# STM32H730_PINOUT.net
KiCad netlist of a schematic drawn in Altium Designer
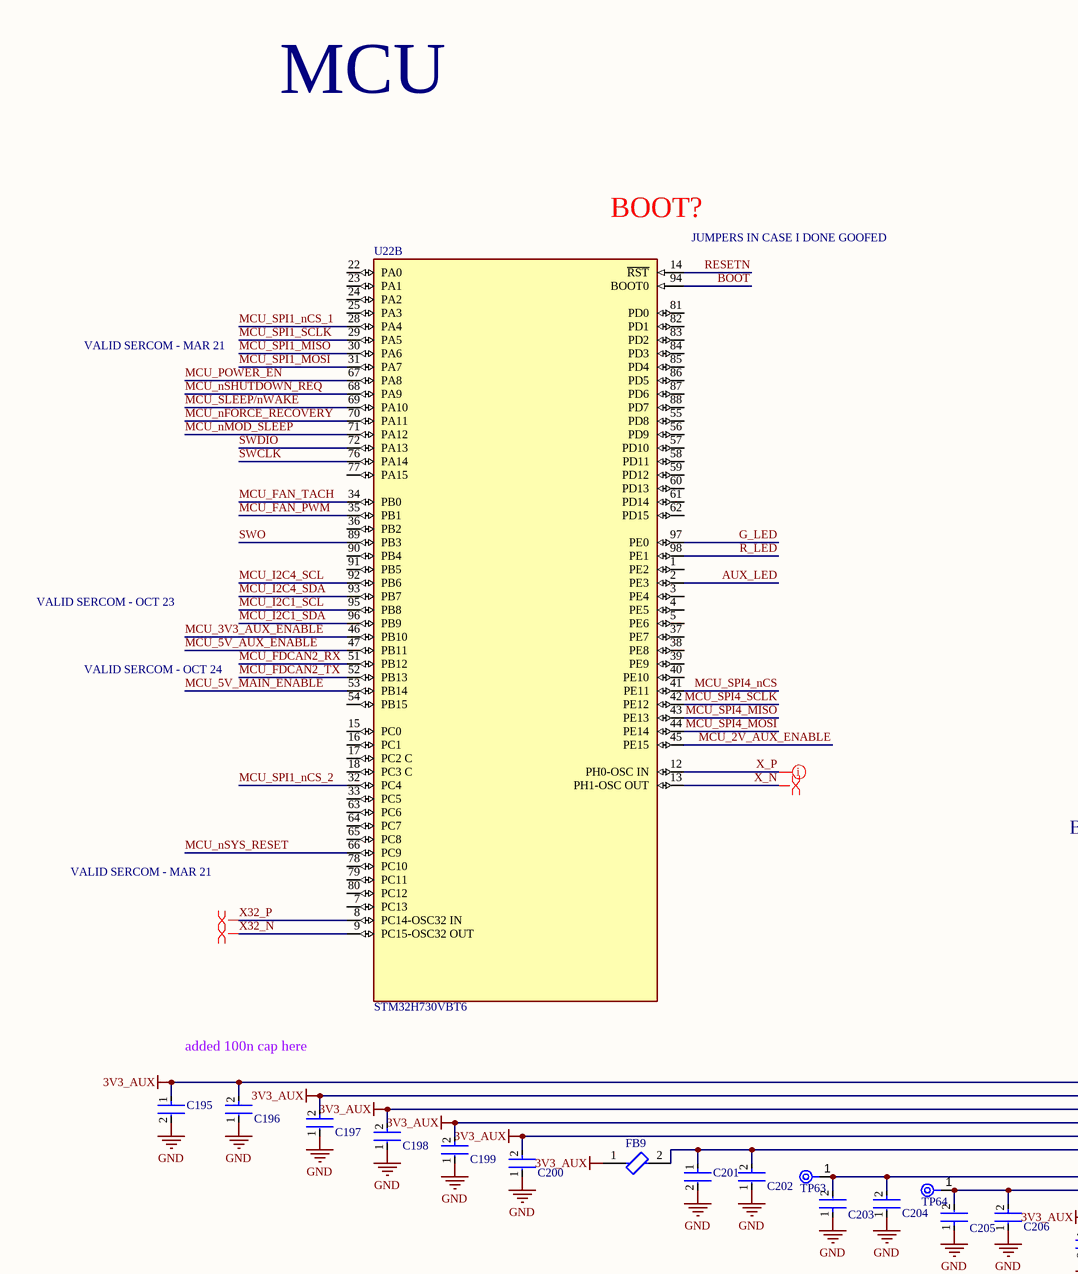
[diagram p0: STM32H730_PINOUT.SchDoc, top left]
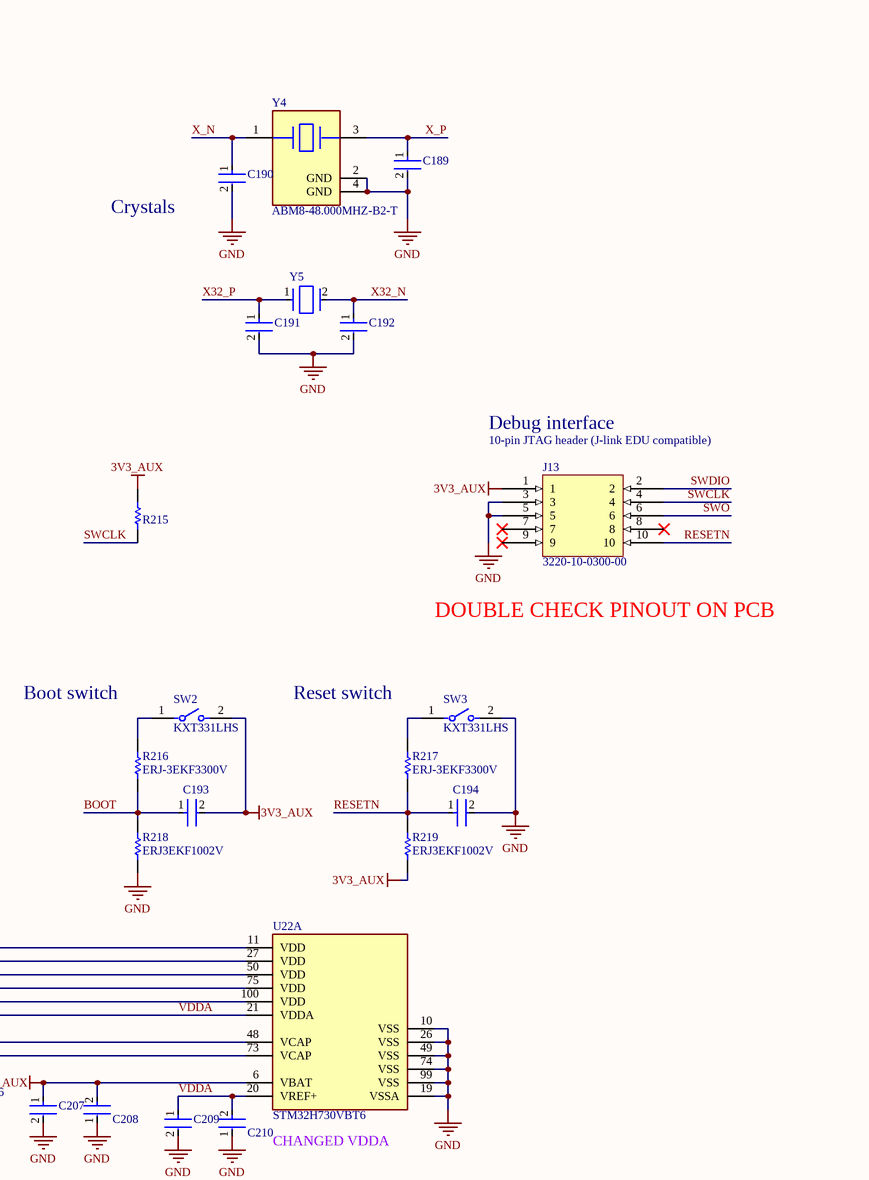
[diagram p1: STM32H730_PINOUT.SchDoc, top middle]
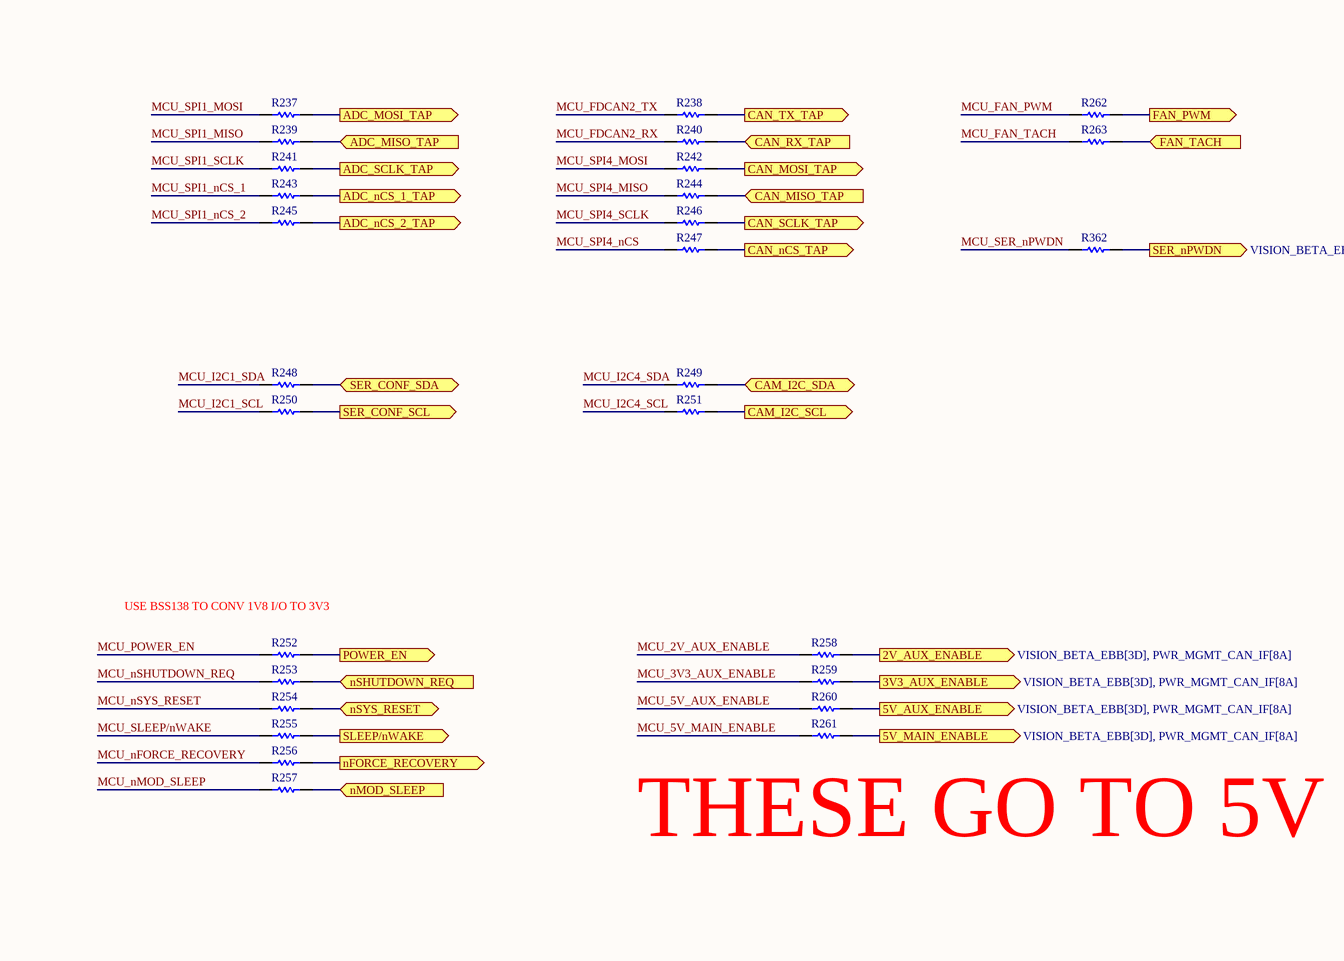
[diagram p2: STM32H730_PINOUT.SchDoc, top right]
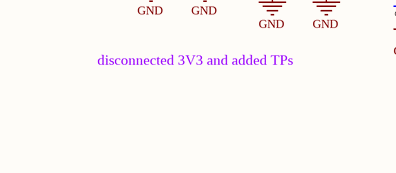
[diagram p3: STM32H730_PINOUT.SchDoc, bottom left]
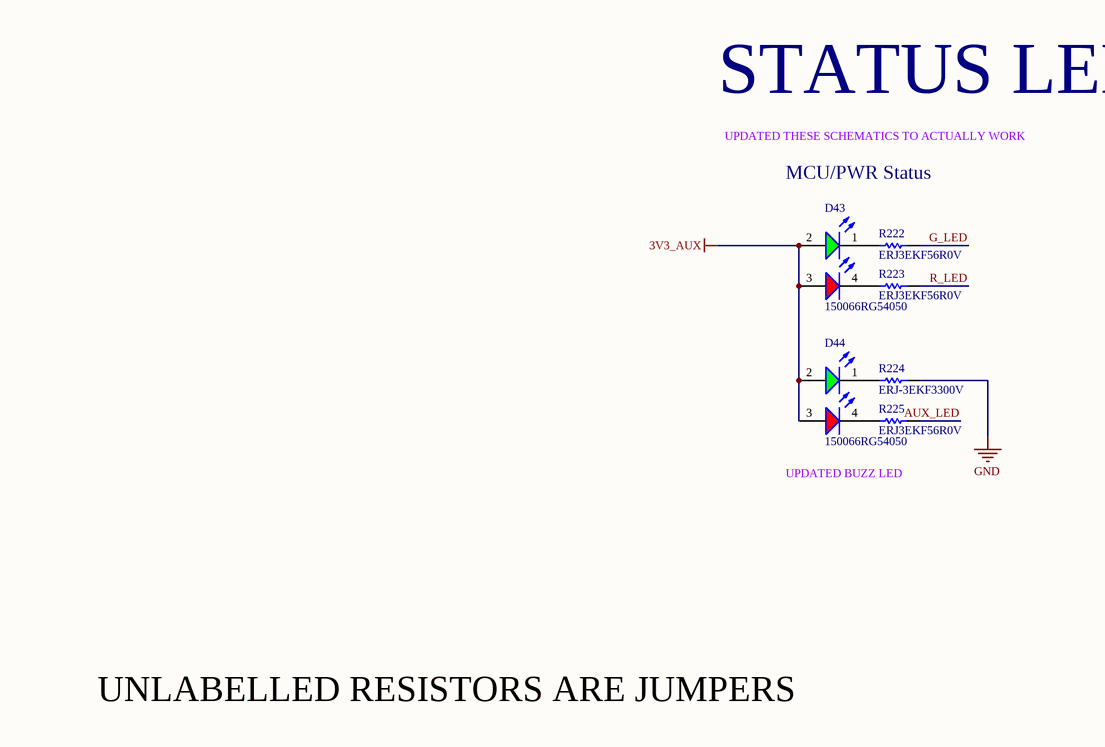
[diagram p4: STM32H730_PINOUT.SchDoc, bottom right]

(export (version "E")
  (design (tool "Eeschema 10.0.6"))
  (components
    (comp (ref "C189")
      (value "C0402C689C5GACTU")
      (footprint "FP-C0402-BB-MFG")
      (description "CAP CER 6.8PF 50V NP0 0402")
      (fields
        (field (name "OCTOPART") "https://octopart.com/c0402c689c5gactu-kemet-9143567")
        (field (name "MANUFACTURER") "Kemet")
      )
      (libsource (lib "Altium Content Vault") (part "b4654b650e69147ec39a6b967a45e02"))
    )
    (comp (ref "C190")
      (value "C0402C689C5GACTU")
      (footprint "FP-C0402-BB-MFG")
      (description "CAP CER 6.8PF 50V NP0 0402")
      (fields
        (field (name "OCTOPART") "https://octopart.com/c0402c689c5gactu-kemet-9143567")
        (field (name "MANUFACTURER") "Kemet")
      )
      (libsource (lib "Altium Content Vault") (part "b4654b650e69147ec39a6b967a45e02"))
    )
    (comp (ref "C191")
      (value "04025A180FAT2A")
      (footprint "FP-0402-L_1_0_1-W_0_5_0_1-IPC_A")
      (description "General Purpose Ceramic Capacitor, 0402, 18pF, 1%, C0G, 30ppm/°C, 50V")
      (fields (field (name "TOLERANCE") "1%"))
      (libsource (lib "Altium Content Vault") (part "b4654b650e69147ec39a6b967a45e02"))
    )
    (comp (ref "C192")
      (value "04025A180FAT2A")
      (footprint "FP-0402-L_1_0_1-W_0_5_0_1-IPC_A")
      (description "General Purpose Ceramic Capacitor, 0402, 18pF, 1%, C0G, 30ppm/°C, 50V")
      (fields (field (name "TOLERANCE") "1%"))
      (libsource (lib "Altium Content Vault") (part "b4654b650e69147ec39a6b967a45e02"))
    )
    (comp (ref "C193")
      (value "C0402C104K8PACTU")
      (footprint "FP-C0402-BB-MFG")
      (description "CAP CER 0.1UF 10V X5R 0402")
      (fields (field (name "MANUFACTURER") "Kemet") (field (name "TOLERANCE") "0.1"))
      (libsource (lib "Altium Content Vault") (part "b4654b650e69147ec39a6b967a45e02"))
    )
    (comp (ref "C194")
      (value "C0402C104K8PACTU")
      (footprint "FP-C0402-BB-MFG")
      (description "CAP CER 0.1UF 10V X5R 0402")
      (fields (field (name "MANUFACTURER") "Kemet") (field (name "TOLERANCE") "0.1"))
      (libsource (lib "Altium Content Vault") (part "b4654b650e69147ec39a6b967a45e02"))
    )
    (comp (ref "C195")
      (value "C1005X5R1A475K050BC")
      (footprint "FP-C1005-050-0_15-MFG")
      (description "CAP CER 4.7UF 10V X5R 0402")
      (fields (field (name "TOLERANCE") "10%"))
      (libsource (lib "Altium Content Vault") (part "b4654b650e69147ec39a6b967a45e02"))
    )
    (comp (ref "C196")
      (value "GRM155R71C104KA88D")
      (footprint "FP-GRM15-MFG")
      (description "CAP CER 0.1UF 16V X7R 0402")
      (fields
        (field (name "TOLERANCE") "10%")
        (field (name "OCTOPART") "https://octopart.com/grm155r71c104ka88d-murata-196880")
      )
      (libsource (lib "Altium Content Vault") (part "236180d848d6139a670b325ea6854c9"))
    )
    (comp (ref "C197")
      (value "GRM155R71C104KA88D")
      (footprint "FP-GRM15-MFG")
      (description "CAP CER 0.1UF 16V X7R 0402")
      (fields
        (field (name "TOLERANCE") "10%")
        (field (name "OCTOPART") "https://octopart.com/grm155r71c104ka88d-murata-196880")
      )
      (libsource (lib "Altium Content Vault") (part "236180d848d6139a670b325ea6854c9"))
    )
    (comp (ref "C198")
      (value "GRM155R71C104KA88D")
      (footprint "FP-GRM15-MFG")
      (description "CAP CER 0.1UF 16V X7R 0402")
      (fields
        (field (name "TOLERANCE") "10%")
        (field (name "OCTOPART") "https://octopart.com/grm155r71c104ka88d-murata-196880")
      )
      (libsource (lib "Altium Content Vault") (part "236180d848d6139a670b325ea6854c9"))
    )
    (comp (ref "C199")
      (value "GRM155R71C104KA88D")
      (footprint "FP-GRM15-MFG")
      (description "CAP CER 0.1UF 16V X7R 0402")
      (fields
        (field (name "TOLERANCE") "10%")
        (field (name "OCTOPART") "https://octopart.com/grm155r71c104ka88d-murata-196880")
      )
      (libsource (lib "Altium Content Vault") (part "236180d848d6139a670b325ea6854c9"))
    )
    (comp (ref "C200")
      (value "GRM155R71C104KA88D")
      (footprint "FP-GRM15-MFG")
      (description "CAP CER 0.1UF 16V X7R 0402")
      (fields
        (field (name "TOLERANCE") "10%")
        (field (name "OCTOPART") "https://octopart.com/grm155r71c104ka88d-murata-196880")
      )
      (libsource (lib "Altium Content Vault") (part "236180d848d6139a670b325ea6854c9"))
    )
    (comp (ref "C201")
      (value "EMK105BJ105KV-F")
      (footprint "FP-0402-L_1_0_0_05-W_0_5-IPC_A")
      (description "None")
      (fields (field (name "TOLERANCE") "10%"))
      (libsource (lib "Altium Content Vault") (part "b4654b650e69147ec39a6b967a45e02"))
    )
    (comp (ref "C202")
      (value "GRM155R71C104KA88D")
      (footprint "FP-GRM15-MFG")
      (description "CAP CER 0.1UF 16V X7R 0402")
      (fields
        (field (name "TOLERANCE") "10%")
        (field (name "OCTOPART") "https://octopart.com/grm155r71c104ka88d-murata-196880")
      )
      (libsource (lib "Altium Content Vault") (part "236180d848d6139a670b325ea6854c9"))
    )
    (comp (ref "C203")
      (value "C1005X7S1A225K050BC")
      (footprint "FP-C1005-050-0_15-0_1-MFG")
      (description "CAP CER 2.2UF 10V X7S 0402")
      (fields (field (name "TOLERANCE") "10%"))
      (libsource (lib "Altium Content Vault") (part "b4654b650e69147ec39a6b967a45e02"))
    )
    (comp (ref "C204")
      (value "GRM155R71C104KA88D")
      (footprint "FP-GRM15-MFG")
      (description "CAP CER 0.1UF 16V X7R 0402")
      (fields
        (field (name "TOLERANCE") "10%")
        (field (name "OCTOPART") "https://octopart.com/grm155r71c104ka88d-murata-196880")
      )
      (libsource (lib "Altium Content Vault") (part "236180d848d6139a670b325ea6854c9"))
    )
    (comp (ref "C205")
      (value "C1005X7S1A225K050BC")
      (footprint "FP-C1005-050-0_15-0_1-MFG")
      (description "CAP CER 2.2UF 10V X7S 0402")
      (fields (field (name "TOLERANCE") "10%"))
      (libsource (lib "Altium Content Vault") (part "b4654b650e69147ec39a6b967a45e02"))
    )
    (comp (ref "C206")
      (value "GRM155R71C104KA88D")
      (footprint "FP-GRM15-MFG")
      (description "CAP CER 0.1UF 16V X7R 0402")
      (fields
        (field (name "TOLERANCE") "10%")
        (field (name "OCTOPART") "https://octopart.com/grm155r71c104ka88d-murata-196880")
      )
      (libsource (lib "Altium Content Vault") (part "236180d848d6139a670b325ea6854c9"))
    )
    (comp (ref "C207")
      (value "EMK105BJ105KV-F")
      (footprint "FP-0402-L_1_0_0_05-W_0_5-IPC_A")
      (description "None")
      (fields (field (name "TOLERANCE") "10%"))
      (libsource (lib "Altium Content Vault") (part "b4654b650e69147ec39a6b967a45e02"))
    )
    (comp (ref "C208")
      (value "GRM155R71C104KA88D")
      (footprint "FP-GRM15-MFG")
      (description "CAP CER 0.1UF 16V X7R 0402")
      (fields
        (field (name "TOLERANCE") "10%")
        (field (name "OCTOPART") "https://octopart.com/grm155r71c104ka88d-murata-196880")
      )
      (libsource (lib "Altium Content Vault") (part "236180d848d6139a670b325ea6854c9"))
    )
    (comp (ref "C209")
      (value "EMK105BJ105KV-F")
      (footprint "FP-0402-L_1_0_0_05-W_0_5-IPC_A")
      (description "None")
      (fields (field (name "TOLERANCE") "10%"))
      (libsource (lib "Altium Content Vault") (part "b4654b650e69147ec39a6b967a45e02"))
    )
    (comp (ref "C210")
      (value "GRM155R71C104KA88D")
      (footprint "FP-GRM15-MFG")
      (description "CAP CER 0.1UF 16V X7R 0402")
      (fields
        (field (name "TOLERANCE") "10%")
        (field (name "OCTOPART") "https://octopart.com/grm155r71c104ka88d-murata-196880")
      )
      (libsource (lib "Altium Content Vault") (part "236180d848d6139a670b325ea6854c9"))
    )
    (comp (ref "D43")
      (value "150066RG54050")
      (footprint "WL-SBCD_0606")
      (description "Led, Red/Grn, 180Mcd/230Mcd, 624Nm/525Nm Rohs Compliant: Yes")
      (fields (field (name "SOURCE") "rgled.SchLib"))
      (libsource (lib "Space Concordia") (part "CMP-004-00034-2"))
    )
    (comp (ref "D44")
      (value "150066RG54050")
      (footprint "WL-SBCD_0606")
      (description "Led, Red/Grn, 180Mcd/230Mcd, 624Nm/525Nm Rohs Compliant: Yes")
      (fields (field (name "SOURCE") "rgled.SchLib"))
      (libsource (lib "Space Concordia") (part "CMP-004-00034-2"))
    )
    (comp (ref "FB9")
      (value "BLM15PX601SN1D")
      (footprint "FP-BLM15-0_05-MFG")
      (description "Chip Ferrite Bead, 0402, 600Ω @ 100MHz, 0.23Ω, 25%, 900mA")
      (fields (field (name "TOLERANCE") "25%"))
      (libsource (lib "Altium Content Vault") (part "5f30dd21d616792df468990f7003faa"))
    )
    (comp (ref "J13")
      (value "3220-10-0300-00")
      (footprint "3220-10-0300-00-Footprint-1")
      (description "CONN HEADER SMD 10POS 1.27MM")
      (libsource (lib "Space Concordia") (part "3220-10-0300-00"))
    )
    (comp (ref "R215")
      (value "ERJ3EKF1002V")
      (footprint "RESC1609X55X30LL15T15")
      (description "Chip Resistor, 10 KOhm, +/- 1%, 0.1 W, -55 to 155 degC, 0603 (1608 Metric), RoHS, Tape and Reel")
      (fields (field (name "TOLERANCE") "1%") (field (name "MANUFACTURER") "Panasonic"))
      (libsource (lib "Altium Content Vault") (part "RES-2"))
    )
    (comp (ref "R216")
      (value "ERJ-3EKF3300V")
      (footprint "RESC1608X55X30LL15T15")
      (description "Chip Resistor, 330 Ohm, +/- 1%, 0.1 W, -55 to 155 degC, 0603 (1608 Metric), RoHS, Tape and Reel")
      (libsource (lib "Altium Content Vault") (part "RES-2"))
    )
    (comp (ref "R217")
      (value "ERJ-3EKF3300V")
      (footprint "RESC1608X55X30LL15T15")
      (description "Chip Resistor, 330 Ohm, +/- 1%, 0.1 W, -55 to 155 degC, 0603 (1608 Metric), RoHS, Tape and Reel")
      (libsource (lib "Altium Content Vault") (part "RES-2"))
    )
    (comp (ref "R218")
      (value "ERJ3EKF1002V")
      (footprint "RESC1609X55X30LL15T15")
      (description "Chip Resistor, 10 KOhm, +/- 1%, 0.1 W, -55 to 155 degC, 0603 (1608 Metric), RoHS, Tape and Reel")
      (fields (field (name "TOLERANCE") "1%") (field (name "MANUFACTURER") "Panasonic"))
      (libsource (lib "Altium Content Vault") (part "RES-2"))
    )
    (comp (ref "R219")
      (value "ERJ3EKF1002V")
      (footprint "RESC1609X55X30LL15T15")
      (description "Chip Resistor, 10 KOhm, +/- 1%, 0.1 W, -55 to 155 degC, 0603 (1608 Metric), RoHS, Tape and Reel")
      (fields (field (name "TOLERANCE") "1%") (field (name "MANUFACTURER") "Panasonic"))
      (libsource (lib "Altium Content Vault") (part "RES-2"))
    )
    (comp (ref "R222")
      (value "ERJ3EKF56R0V")
      (footprint "RESC1608X55X30NL15T15")
      (fields (field (name "MANUFACTURER") "Panasonic"))
      (libsource (lib "Altium Content Vault") (part "RES"))
    )
    (comp (ref "R223")
      (value "ERJ3EKF56R0V")
      (footprint "RESC1608X55X30NL15T15")
      (fields (field (name "MANUFACTURER") "Panasonic"))
      (libsource (lib "Altium Content Vault") (part "RES"))
    )
    (comp (ref "R224")
      (value "ERJ-3EKF3300V")
      (footprint "RESC1608X55X30LL15T15")
      (description "Chip Resistor, 330 Ohm, +/- 1%, 0.1 W, -55 to 155 degC, 0603 (1608 Metric), RoHS, Tape and Reel")
      (libsource (lib "Altium Content Vault") (part "RES-2"))
    )
    (comp (ref "R225")
      (value "ERJ3EKF56R0V")
      (footprint "RESC1608X55X30NL15T15")
      (fields (field (name "MANUFACTURER") "Panasonic"))
      (libsource (lib "Altium Content Vault") (part "RES"))
    )
    (comp (ref "R237")
      (value "0402 JUMPER")
      (footprint "RESC1005X40X25ML05T05")
      (description "READ THE NAME")
      (libsource (lib "Space Concordia") (part "CMP-009-00206-2"))
    )
    (comp (ref "R238")
      (value "0402 JUMPER")
      (footprint "RESC1005X40X25ML05T05")
      (description "READ THE NAME")
      (libsource (lib "Space Concordia") (part "CMP-009-00206-2"))
    )
    (comp (ref "R239")
      (value "0402 JUMPER")
      (footprint "RESC1005X40X25ML05T05")
      (description "READ THE NAME")
      (libsource (lib "Space Concordia") (part "CMP-009-00206-2"))
    )
    (comp (ref "R240")
      (value "0402 JUMPER")
      (footprint "RESC1005X40X25ML05T05")
      (description "READ THE NAME")
      (libsource (lib "Space Concordia") (part "CMP-009-00206-2"))
    )
    (comp (ref "R241")
      (value "0402 JUMPER")
      (footprint "RESC1005X40X25ML05T05")
      (description "READ THE NAME")
      (libsource (lib "Space Concordia") (part "CMP-009-00206-2"))
    )
    (comp (ref "R242")
      (value "0402 JUMPER")
      (footprint "RESC1005X40X25ML05T05")
      (description "READ THE NAME")
      (libsource (lib "Space Concordia") (part "CMP-009-00206-2"))
    )
    (comp (ref "R243")
      (value "0402 JUMPER")
      (footprint "RESC1005X40X25ML05T05")
      (description "READ THE NAME")
      (libsource (lib "Space Concordia") (part "CMP-009-00206-2"))
    )
    (comp (ref "R244")
      (value "0402 JUMPER")
      (footprint "RESC1005X40X25ML05T05")
      (description "READ THE NAME")
      (libsource (lib "Space Concordia") (part "CMP-009-00206-2"))
    )
    (comp (ref "R245")
      (value "0402 JUMPER")
      (footprint "RESC1005X40X25ML05T05")
      (description "READ THE NAME")
      (libsource (lib "Space Concordia") (part "CMP-009-00206-2"))
    )
    (comp (ref "R246")
      (value "0402 JUMPER")
      (footprint "RESC1005X40X25ML05T05")
      (description "READ THE NAME")
      (libsource (lib "Space Concordia") (part "CMP-009-00206-2"))
    )
    (comp (ref "R247")
      (value "0402 JUMPER")
      (footprint "RESC1005X40X25ML05T05")
      (description "READ THE NAME")
      (libsource (lib "Space Concordia") (part "CMP-009-00206-2"))
    )
    (comp (ref "R248")
      (value "0402 JUMPER")
      (footprint "RESC1005X40X25ML05T05")
      (description "READ THE NAME")
      (libsource (lib "Space Concordia") (part "CMP-009-00206-2"))
    )
    (comp (ref "R249")
      (value "0402 JUMPER")
      (footprint "RESC1005X40X25ML05T05")
      (description "READ THE NAME")
      (libsource (lib "Space Concordia") (part "CMP-009-00206-2"))
    )
    (comp (ref "R250")
      (value "0402 JUMPER")
      (footprint "RESC1005X40X25ML05T05")
      (description "READ THE NAME")
      (libsource (lib "Space Concordia") (part "CMP-009-00206-2"))
    )
    (comp (ref "R251")
      (value "0402 JUMPER")
      (footprint "RESC1005X40X25ML05T05")
      (description "READ THE NAME")
      (libsource (lib "Space Concordia") (part "CMP-009-00206-2"))
    )
    (comp (ref "R252")
      (value "0402 JUMPER")
      (footprint "RESC1005X40X25ML05T05")
      (description "READ THE NAME")
      (libsource (lib "Space Concordia") (part "CMP-009-00206-2"))
    )
    (comp (ref "R253")
      (value "0402 JUMPER")
      (footprint "RESC1005X40X25ML05T05")
      (description "READ THE NAME")
      (libsource (lib "Space Concordia") (part "CMP-009-00206-2"))
    )
    (comp (ref "R254")
      (value "0402 JUMPER")
      (footprint "RESC1005X40X25ML05T05")
      (description "READ THE NAME")
      (libsource (lib "Space Concordia") (part "CMP-009-00206-2"))
    )
    (comp (ref "R255")
      (value "0402 JUMPER")
      (footprint "RESC1005X40X25ML05T05")
      (description "READ THE NAME")
      (libsource (lib "Space Concordia") (part "CMP-009-00206-2"))
    )
    (comp (ref "R256")
      (value "0402 JUMPER")
      (footprint "RESC1005X40X25ML05T05")
      (description "READ THE NAME")
      (libsource (lib "Space Concordia") (part "CMP-009-00206-2"))
    )
    (comp (ref "R257")
      (value "0402 JUMPER")
      (footprint "RESC1005X40X25ML05T05")
      (description "READ THE NAME")
      (libsource (lib "Space Concordia") (part "CMP-009-00206-2"))
    )
    (comp (ref "R258")
      (value "0402 JUMPER")
      (footprint "RESC1005X40X25ML05T05")
      (description "READ THE NAME")
      (libsource (lib "Space Concordia") (part "CMP-009-00206-2"))
    )
    (comp (ref "R259")
      (value "0402 JUMPER")
      (footprint "RESC1005X40X25ML05T05")
      (description "READ THE NAME")
      (libsource (lib "Space Concordia") (part "CMP-009-00206-2"))
    )
    (comp (ref "R260")
      (value "0402 JUMPER")
      (footprint "RESC1005X40X25ML05T05")
      (description "READ THE NAME")
      (libsource (lib "Space Concordia") (part "CMP-009-00206-2"))
    )
    (comp (ref "R261")
      (value "0402 JUMPER")
      (footprint "RESC1005X40X25ML05T05")
      (description "READ THE NAME")
      (libsource (lib "Space Concordia") (part "CMP-009-00206-2"))
    )
    (comp (ref "R262")
      (value "0402 JUMPER")
      (footprint "RESC1005X40X25ML05T05")
      (description "READ THE NAME")
      (libsource (lib "Space Concordia") (part "CMP-009-00206-2"))
    )
    (comp (ref "R263")
      (value "0402 JUMPER")
      (footprint "RESC1005X40X25ML05T05")
      (description "READ THE NAME")
      (libsource (lib "Space Concordia") (part "CMP-009-00206-2"))
    )
    (comp (ref "R362")
      (value "0402 JUMPER")
      (footprint "RESC1005X40X25ML05T05")
      (description "READ THE NAME")
      (libsource (lib "Space Concordia") (part "CMP-009-00206-2"))
    )
    (comp (ref "SW2")
      (value "KXT331LHS")
      (footprint "FP-KXT331LHS-MFG")
      (description "SWITCH TACTILE SPST-NO 0.02A 15V")
      (libsource (lib "Altium Content Vault") (part "bb27bde45df87f1f469753f287ef5ae"))
    )
    (comp (ref "SW3")
      (value "KXT331LHS")
      (footprint "FP-KXT331LHS-MFG")
      (description "SWITCH TACTILE SPST-NO 0.02A 15V")
      (libsource (lib "Altium Content Vault") (part "bb27bde45df87f1f469753f287ef5ae"))
    )
    (comp (ref "TP63")
      (value "TPAD6R")
      (footprint "New footprint 1")
      (description "Test Point .6mm")
      (libsource (lib "Space Concordia") (part "TP"))
    )
    (comp (ref "TP64")
      (value "TPAD6R")
      (footprint "New footprint 1")
      (description "Test Point .6mm")
      (libsource (lib "Space Concordia") (part "TP"))
    )
    (comp (ref "U22")
      (value "STM32H730VBT6")
      (footprint "FP-LQFP100-1L-IPC_C")
      (description "IC MCU 32BIT 128KB FLASH 100LQFP")
      (libsource (lib "Altium Content Vault") (part "44dc6501260a4d92b846760feb66c20"))
    )
    (comp (ref "Y4")
      (value "ABM8-48.000MHZ-B2-T")
      (footprint "FP-ABM8-MFG")
      (description "Crystal 48MHz ±20ppm 18pF SMD-4 3.2mm x 2.5mm")
      (fields (field (name "TOLERANCE") "20ppm"))
      (libsource (lib "Altium Content Vault") (part "dfdb7f9a12507849fb681da9a70121c"))
    )
    (comp (ref "Y5")
      (value "ECS-.327-12.5-1210-TR")
      (footprint "FP-ECX-1210-MFG")
      (description "CRYSTAL 32.7680KHZ 12.5PF SMD")
      (fields
        (field (name "OCTOPART") "https://octopart.com/ecs-.327-12.5-1210-tr-ecs+international-81221340")
        (field (name "TOLERANCE") "20ppm")
      )
      (libsource (lib "Altium Content Vault") (part "99724985039315a44fd0d1401b84e49"))
    )
  )
  (nets
    (net (code "1") (name "/2V_AUX_ENABLE") (class "Default")
      (node (ref "R258") (pin "2") (pinfunction "2_2") (pintype "passive"))
    )
    (net (code "2") (name "/3V3_AUX_ENABLE") (class "Default")
      (node (ref "R259") (pin "2") (pinfunction "2_2") (pintype "passive"))
    )
    (net (code "3") (name "/5V_AUX_ENABLE") (class "Default")
      (node (ref "R260") (pin "2") (pinfunction "2_2") (pintype "passive"))
    )
    (net (code "4") (name "/5V_MAIN_ENABLE") (class "Default")
      (node (ref "R261") (pin "2") (pinfunction "2_2") (pintype "passive"))
    )
    (net (code "5") (name "/ADC_MISO_TAP") (class "Default")
      (node (ref "R239") (pin "2") (pinfunction "2_2") (pintype "passive"))
    )
    (net (code "6") (name "/ADC_MOSI_TAP") (class "Default")
      (node (ref "R237") (pin "2") (pinfunction "2_2") (pintype "passive"))
    )
    (net (code "7") (name "/ADC_SCLK_TAP") (class "Default")
      (node (ref "R241") (pin "2") (pinfunction "2_2") (pintype "passive"))
    )
    (net (code "8") (name "/ADC_nCS_1_TAP") (class "Default")
      (node (ref "R243") (pin "2") (pinfunction "2_2") (pintype "passive"))
    )
    (net (code "9") (name "/ADC_nCS_2_TAP") (class "Default")
      (node (ref "R245") (pin "2") (pinfunction "2_2") (pintype "passive"))
    )
    (net (code "10") (name "/AUX_LED") (class "Default")
      (node (ref "R225") (pin "1") (pinfunction "1_1") (pintype "passive"))
      (node (ref "U22") (pin "2") (pinfunction "PE3_2") (pintype "bidirectional"))
    )
    (net (code "11") (name "/BOOT") (class "Default")
      (node (ref "C193") (pin "1") (pinfunction "1_1") (pintype "passive"))
      (node (ref "R216") (pin "1") (pinfunction "1_1") (pintype "passive"))
      (node (ref "R218") (pin "2") (pinfunction "2_2") (pintype "passive"))
      (node (ref "U22") (pin "94") (pinfunction "BOOT0_94") (pintype "input"))
    )
    (net (code "12") (name "/CAM_I2C_SCL") (class "Default")
      (node (ref "R251") (pin "2") (pinfunction "2_2") (pintype "passive"))
    )
    (net (code "13") (name "/CAM_I2C_SDA") (class "Default")
      (node (ref "R249") (pin "2") (pinfunction "2_2") (pintype "passive"))
    )
    (net (code "14") (name "/CAN_MISO_TAP") (class "Default")
      (node (ref "R244") (pin "2") (pinfunction "2_2") (pintype "passive"))
    )
    (net (code "15") (name "/CAN_MOSI_TAP") (class "Default")
      (node (ref "R242") (pin "2") (pinfunction "2_2") (pintype "passive"))
    )
    (net (code "16") (name "/CAN_RX_TAP") (class "Default")
      (node (ref "R240") (pin "2") (pinfunction "2_2") (pintype "passive"))
    )
    (net (code "17") (name "/CAN_SCLK_TAP") (class "Default")
      (node (ref "R246") (pin "2") (pinfunction "2_2") (pintype "passive"))
    )
    (net (code "18") (name "/CAN_TX_TAP") (class "Default")
      (node (ref "R238") (pin "2") (pinfunction "2_2") (pintype "passive"))
    )
    (net (code "19") (name "/CAN_nCS_TAP") (class "Default")
      (node (ref "R247") (pin "2") (pinfunction "2_2") (pintype "passive"))
    )
    (net (code "20") (name "/FAN_PWM") (class "Default")
      (node (ref "R262") (pin "2") (pinfunction "2_2") (pintype "passive"))
    )
    (net (code "21") (name "/FAN_TACH") (class "Default")
      (node (ref "R263") (pin "2") (pinfunction "2_2") (pintype "passive"))
    )
    (net (code "22") (name "/G_LED") (class "Default")
      (node (ref "R222") (pin "1") (pinfunction "1_1") (pintype "passive"))
      (node (ref "U22") (pin "97") (pinfunction "PE0_97") (pintype "bidirectional"))
    )
    (net (code "23") (name "/MCU_2V_AUX_ENABLE") (class "Default")
      (node (ref "R258") (pin "1") (pinfunction "1_1") (pintype "passive"))
      (node (ref "U22") (pin "45") (pinfunction "PE15_45") (pintype "bidirectional"))
    )
    (net (code "24") (name "/MCU_3V3_AUX_ENABLE") (class "Default")
      (node (ref "R259") (pin "1") (pinfunction "1_1") (pintype "passive"))
      (node (ref "U22") (pin "46") (pinfunction "PB10_46") (pintype "bidirectional"))
    )
    (net (code "25") (name "/MCU_5V_AUX_ENABLE") (class "Default")
      (node (ref "R260") (pin "1") (pinfunction "1_1") (pintype "passive"))
      (node (ref "U22") (pin "47") (pinfunction "PB11_47") (pintype "bidirectional"))
    )
    (net (code "26") (name "/MCU_5V_MAIN_ENABLE") (class "Default")
      (node (ref "R261") (pin "1") (pinfunction "1_1") (pintype "passive"))
      (node (ref "U22") (pin "53") (pinfunction "PB14_53") (pintype "bidirectional"))
    )
    (net (code "27") (name "/MCU_FAN_PWM") (class "Default")
      (node (ref "R262") (pin "1") (pinfunction "1_1") (pintype "passive"))
      (node (ref "U22") (pin "35") (pinfunction "PB1_35") (pintype "bidirectional"))
    )
    (net (code "28") (name "/MCU_FAN_TACH") (class "Default")
      (node (ref "R263") (pin "1") (pinfunction "1_1") (pintype "passive"))
      (node (ref "U22") (pin "34") (pinfunction "PB0_34") (pintype "bidirectional"))
    )
    (net (code "29") (name "/MCU_FDCAN2_RX") (class "Default")
      (node (ref "R240") (pin "1") (pinfunction "1_1") (pintype "passive"))
      (node (ref "U22") (pin "51") (pinfunction "PB12_51") (pintype "bidirectional"))
    )
    (net (code "30") (name "/MCU_FDCAN2_TX") (class "Default")
      (node (ref "R238") (pin "1") (pinfunction "1_1") (pintype "passive"))
      (node (ref "U22") (pin "52") (pinfunction "PB13_52") (pintype "bidirectional"))
    )
    (net (code "31") (name "/MCU_I2C1_SCL") (class "Default")
      (node (ref "R250") (pin "1") (pinfunction "1_1") (pintype "passive"))
      (node (ref "U22") (pin "95") (pinfunction "PB8_95") (pintype "bidirectional"))
    )
    (net (code "32") (name "/MCU_I2C1_SDA") (class "Default")
      (node (ref "R248") (pin "1") (pinfunction "1_1") (pintype "passive"))
      (node (ref "U22") (pin "96") (pinfunction "PB9_96") (pintype "bidirectional"))
    )
    (net (code "33") (name "/MCU_I2C4_SCL") (class "Default")
      (node (ref "R251") (pin "1") (pinfunction "1_1") (pintype "passive"))
      (node (ref "U22") (pin "92") (pinfunction "PB6_92") (pintype "bidirectional"))
    )
    (net (code "34") (name "/MCU_I2C4_SDA") (class "Default")
      (node (ref "R249") (pin "1") (pinfunction "1_1") (pintype "passive"))
      (node (ref "U22") (pin "93") (pinfunction "PB7_93") (pintype "bidirectional"))
    )
    (net (code "35") (name "/MCU_POWER_EN") (class "Default")
      (node (ref "R252") (pin "1") (pinfunction "1_1") (pintype "passive"))
      (node (ref "U22") (pin "67") (pinfunction "PA8_67") (pintype "bidirectional"))
    )
    (net (code "36") (name "/MCU_SER_nPWDN") (class "Default")
      (node (ref "R362") (pin "1") (pinfunction "1_1") (pintype "passive"))
    )
    (net (code "37") (name "/MCU_SLEEP{slash}nWAKE") (class "Default")
      (node (ref "R255") (pin "1") (pinfunction "1_1") (pintype "passive"))
      (node (ref "U22") (pin "69") (pinfunction "PA10_69") (pintype "bidirectional"))
    )
    (net (code "38") (name "/MCU_SPI1_MISO") (class "Default")
      (node (ref "R239") (pin "1") (pinfunction "1_1") (pintype "passive"))
      (node (ref "U22") (pin "30") (pinfunction "PA6_30") (pintype "bidirectional"))
    )
    (net (code "39") (name "/MCU_SPI1_MOSI") (class "Default")
      (node (ref "R237") (pin "1") (pinfunction "1_1") (pintype "passive"))
      (node (ref "U22") (pin "31") (pinfunction "PA7_31") (pintype "bidirectional"))
    )
    (net (code "40") (name "/MCU_SPI1_SCLK") (class "Default")
      (node (ref "R241") (pin "1") (pinfunction "1_1") (pintype "passive"))
      (node (ref "U22") (pin "29") (pinfunction "PA5_29") (pintype "bidirectional"))
    )
    (net (code "41") (name "/MCU_SPI1_nCS_1") (class "Default")
      (node (ref "R243") (pin "1") (pinfunction "1_1") (pintype "passive"))
      (node (ref "U22") (pin "28") (pinfunction "PA4_28") (pintype "bidirectional"))
    )
    (net (code "42") (name "/MCU_SPI1_nCS_2") (class "Default")
      (node (ref "R245") (pin "1") (pinfunction "1_1") (pintype "passive"))
      (node (ref "U22") (pin "32") (pinfunction "PC4_32") (pintype "bidirectional"))
    )
    (net (code "43") (name "/MCU_SPI4_MISO") (class "Default")
      (node (ref "R244") (pin "1") (pinfunction "1_1") (pintype "passive"))
      (node (ref "U22") (pin "43") (pinfunction "PE13_43") (pintype "bidirectional"))
    )
    (net (code "44") (name "/MCU_SPI4_MOSI") (class "Default")
      (node (ref "R242") (pin "1") (pinfunction "1_1") (pintype "passive"))
      (node (ref "U22") (pin "44") (pinfunction "PE14_44") (pintype "bidirectional"))
    )
    (net (code "45") (name "/MCU_SPI4_SCLK") (class "Default")
      (node (ref "R246") (pin "1") (pinfunction "1_1") (pintype "passive"))
      (node (ref "U22") (pin "42") (pinfunction "PE12_42") (pintype "bidirectional"))
    )
    (net (code "46") (name "/MCU_SPI4_nCS") (class "Default")
      (node (ref "R247") (pin "1") (pinfunction "1_1") (pintype "passive"))
      (node (ref "U22") (pin "41") (pinfunction "PE11_41") (pintype "bidirectional"))
    )
    (net (code "47") (name "/MCU_nFORCE_RECOVERY") (class "Default")
      (node (ref "R256") (pin "1") (pinfunction "1_1") (pintype "passive"))
      (node (ref "U22") (pin "70") (pinfunction "PA11_70") (pintype "bidirectional"))
    )
    (net (code "48") (name "/MCU_nMOD_SLEEP") (class "Default")
      (node (ref "R257") (pin "1") (pinfunction "1_1") (pintype "passive"))
      (node (ref "U22") (pin "71") (pinfunction "PA12_71") (pintype "bidirectional"))
    )
    (net (code "49") (name "/MCU_nSHUTDOWN_REQ") (class "Default")
      (node (ref "R253") (pin "1") (pinfunction "1_1") (pintype "passive"))
      (node (ref "U22") (pin "68") (pinfunction "PA9_68") (pintype "bidirectional"))
    )
    (net (code "50") (name "/MCU_nSYS_RESET") (class "Default")
      (node (ref "R254") (pin "1") (pinfunction "1_1") (pintype "passive"))
      (node (ref "U22") (pin "66") (pinfunction "PC9_66") (pintype "bidirectional"))
    )
    (net (code "51") (name "/POWER_EN") (class "Default")
      (node (ref "R252") (pin "2") (pinfunction "2_2") (pintype "passive"))
    )
    (net (code "52") (name "/RESETN") (class "Default")
      (node (ref "C194") (pin "1") (pinfunction "1_1") (pintype "passive"))
      (node (ref "J13") (pin "10") (pinfunction "10_10") (pintype "input"))
      (node (ref "R217") (pin "1") (pinfunction "1_1") (pintype "passive"))
      (node (ref "R219") (pin "2") (pinfunction "2_2") (pintype "passive"))
      (node (ref "U22") (pin "14") (pinfunction "~{RST}_14") (pintype "input"))
    )
    (net (code "53") (name "/R_LED") (class "Default")
      (node (ref "R223") (pin "1") (pinfunction "1_1") (pintype "passive"))
      (node (ref "U22") (pin "98") (pinfunction "PE1_98") (pintype "bidirectional"))
    )
    (net (code "54") (name "/SER_CONF_SCL") (class "Default")
      (node (ref "R250") (pin "2") (pinfunction "2_2") (pintype "passive"))
    )
    (net (code "55") (name "/SER_CONF_SDA") (class "Default")
      (node (ref "R248") (pin "2") (pinfunction "2_2") (pintype "passive"))
    )
    (net (code "56") (name "/SER_nPWDN") (class "Default")
      (node (ref "R362") (pin "2") (pinfunction "2_2") (pintype "passive"))
    )
    (net (code "57") (name "/SLEEP{slash}nWAKE") (class "Default")
      (node (ref "R255") (pin "2") (pinfunction "2_2") (pintype "passive"))
    )
    (net (code "58") (name "/SWCLK") (class "Default")
      (node (ref "J13") (pin "4") (pinfunction "4_4") (pintype "input"))
      (node (ref "R215") (pin "2") (pinfunction "2_2") (pintype "passive"))
      (node (ref "U22") (pin "76") (pinfunction "PA14_76") (pintype "bidirectional"))
    )
    (net (code "59") (name "/SWDIO") (class "Default")
      (node (ref "J13") (pin "2") (pinfunction "2_2") (pintype "input"))
      (node (ref "U22") (pin "72") (pinfunction "PA13_72") (pintype "bidirectional"))
    )
    (net (code "60") (name "/SWO") (class "Default")
      (node (ref "J13") (pin "6") (pinfunction "6_6") (pintype "input"))
      (node (ref "U22") (pin "89") (pinfunction "PB3_89") (pintype "bidirectional"))
    )
    (net (code "61") (name "/VDDA") (class "Default")
      (node (ref "C201") (pin "1") (pinfunction "1_1") (pintype "passive"))
      (node (ref "C202") (pin "2") (pinfunction "2_2") (pintype "passive"))
      (node (ref "C209") (pin "1") (pinfunction "1_1") (pintype "passive"))
      (node (ref "C210") (pin "2") (pinfunction "2_2") (pintype "passive"))
      (node (ref "FB9") (pin "2") (pinfunction "2_2") (pintype "passive"))
      (node (ref "U22") (pin "20") (pinfunction "VREF+_20") (pintype "power_in"))
      (node (ref "U22") (pin "21") (pinfunction "VDDA_21") (pintype "power_in"))
    )
    (net (code "62") (name "/X32_N") (class "Default")
      (node (ref "C192") (pin "1") (pinfunction "1_1") (pintype "passive"))
      (node (ref "U22") (pin "9") (pinfunction "PC15-OSC32_OUT_9") (pintype "bidirectional"))
      (node (ref "Y5") (pin "2") (pinfunction "Out/In_2") (pintype "passive"))
    )
    (net (code "63") (name "/X32_P") (class "Default")
      (node (ref "C191") (pin "1") (pinfunction "1_1") (pintype "passive"))
      (node (ref "U22") (pin "8") (pinfunction "PC14-OSC32_IN_8") (pintype "bidirectional"))
      (node (ref "Y5") (pin "1") (pinfunction "In/Out_1") (pintype "passive"))
    )
    (net (code "64") (name "/X_N") (class "Default")
      (node (ref "C190") (pin "1") (pinfunction "1_1") (pintype "passive"))
      (node (ref "U22") (pin "13") (pinfunction "PH1-OSC_OUT_13") (pintype "bidirectional"))
      (node (ref "Y4") (pin "1") (pinfunction "1_1") (pintype "passive"))
    )
    (net (code "65") (name "/X_P") (class "Default")
      (node (ref "C189") (pin "1") (pinfunction "1_1") (pintype "passive"))
      (node (ref "U22") (pin "12") (pinfunction "PH0-OSC_IN_12") (pintype "bidirectional"))
      (node (ref "Y4") (pin "3") (pinfunction "3_3") (pintype "passive"))
    )
    (net (code "66") (name "/nFORCE_RECOVERY") (class "Default")
      (node (ref "R256") (pin "2") (pinfunction "2_2") (pintype "passive"))
    )
    (net (code "67") (name "/nMOD_SLEEP") (class "Default")
      (node (ref "R257") (pin "2") (pinfunction "2_2") (pintype "passive"))
    )
    (net (code "68") (name "/nSHUTDOWN_REQ") (class "Default")
      (node (ref "R253") (pin "2") (pinfunction "2_2") (pintype "passive"))
    )
    (net (code "69") (name "/nSYS_RESET") (class "Default")
      (node (ref "R254") (pin "2") (pinfunction "2_2") (pintype "passive"))
    )
    (net (code "70") (name "3V3_AUX") (class "Default")
      (node (ref "C193") (pin "2") (pinfunction "2_2") (pintype "passive"))
      (node (ref "C195") (pin "1") (pinfunction "1_1") (pintype "passive"))
      (node (ref "C196") (pin "2") (pinfunction "2_2") (pintype "passive"))
      (node (ref "C197") (pin "2") (pinfunction "2_2") (pintype "passive"))
      (node (ref "C198") (pin "2") (pinfunction "2_2") (pintype "passive"))
      (node (ref "C199") (pin "2") (pinfunction "2_2") (pintype "passive"))
      (node (ref "C200") (pin "2") (pinfunction "2_2") (pintype "passive"))
      (node (ref "C207") (pin "1") (pinfunction "1_1") (pintype "passive"))
      (node (ref "C208") (pin "2") (pinfunction "2_2") (pintype "passive"))
      (node (ref "D43") (pin "2") (pinfunction "A_2") (pintype "passive"))
      (node (ref "D43") (pin "3") (pinfunction "A_3") (pintype "passive"))
      (node (ref "D44") (pin "2") (pinfunction "A_2") (pintype "passive"))
      (node (ref "D44") (pin "3") (pinfunction "A_3") (pintype "passive"))
      (node (ref "FB9") (pin "1") (pinfunction "1_1") (pintype "passive"))
      (node (ref "J13") (pin "1") (pinfunction "1_1") (pintype "input"))
      (node (ref "R215") (pin "1") (pinfunction "1_1") (pintype "passive"))
      (node (ref "R219") (pin "1") (pinfunction "1_1") (pintype "passive"))
      (node (ref "SW2") (pin "2") (pinfunction "2_2") (pintype "passive"))
      (node (ref "U22") (pin "100") (pinfunction "VDD_100") (pintype "power_in"))
      (node (ref "U22") (pin "11") (pinfunction "VDD_11") (pintype "power_in"))
      (node (ref "U22") (pin "27") (pinfunction "VDD_27") (pintype "power_in"))
      (node (ref "U22") (pin "50") (pinfunction "VDD_50") (pintype "power_in"))
      (node (ref "U22") (pin "6") (pinfunction "VBAT_6") (pintype "power_in"))
      (node (ref "U22") (pin "75") (pinfunction "VDD_75") (pintype "power_in"))
    )
    (net (code "71") (name "GND") (class "Default")
      (node (ref "C189") (pin "2") (pinfunction "2_2") (pintype "passive"))
      (node (ref "C190") (pin "2") (pinfunction "2_2") (pintype "passive"))
      (node (ref "C191") (pin "2") (pinfunction "2_2") (pintype "passive"))
      (node (ref "C192") (pin "2") (pinfunction "2_2") (pintype "passive"))
      (node (ref "C194") (pin "2") (pinfunction "2_2") (pintype "passive"))
      (node (ref "C195") (pin "2") (pinfunction "2_2") (pintype "passive"))
      (node (ref "C196") (pin "1") (pinfunction "1_1") (pintype "passive"))
      (node (ref "C197") (pin "1") (pinfunction "1_1") (pintype "passive"))
      (node (ref "C198") (pin "1") (pinfunction "1_1") (pintype "passive"))
      (node (ref "C199") (pin "1") (pinfunction "1_1") (pintype "passive"))
      (node (ref "C200") (pin "1") (pinfunction "1_1") (pintype "passive"))
      (node (ref "C201") (pin "2") (pinfunction "2_2") (pintype "passive"))
      (node (ref "C202") (pin "1") (pinfunction "1_1") (pintype "passive"))
      (node (ref "C203") (pin "1") (pinfunction "1_1") (pintype "passive"))
      (node (ref "C204") (pin "1") (pinfunction "1_1") (pintype "passive"))
      (node (ref "C205") (pin "1") (pinfunction "1_1") (pintype "passive"))
      (node (ref "C206") (pin "1") (pinfunction "1_1") (pintype "passive"))
      (node (ref "C207") (pin "2") (pinfunction "2_2") (pintype "passive"))
      (node (ref "C208") (pin "1") (pinfunction "1_1") (pintype "passive"))
      (node (ref "C209") (pin "2") (pinfunction "2_2") (pintype "passive"))
      (node (ref "C210") (pin "1") (pinfunction "1_1") (pintype "passive"))
      (node (ref "J13") (pin "3") (pinfunction "3_3") (pintype "input"))
      (node (ref "J13") (pin "5") (pinfunction "5_5") (pintype "input"))
      (node (ref "R218") (pin "1") (pinfunction "1_1") (pintype "passive"))
      (node (ref "R224") (pin "2") (pinfunction "2_2") (pintype "passive"))
      (node (ref "SW3") (pin "2") (pinfunction "2_2") (pintype "passive"))
      (node (ref "U22") (pin "10") (pinfunction "VSS_10") (pintype "power_in"))
      (node (ref "U22") (pin "19") (pinfunction "VSSA_19") (pintype "power_in"))
      (node (ref "U22") (pin "26") (pinfunction "VSS_26") (pintype "power_in"))
      (node (ref "U22") (pin "49") (pinfunction "VSS_49") (pintype "power_in"))
      (node (ref "U22") (pin "74") (pinfunction "VSS_74") (pintype "power_in"))
      (node (ref "U22") (pin "99") (pinfunction "VSS_99") (pintype "power_in"))
      (node (ref "Y4") (pin "2") (pinfunction "GND_2") (pintype "power_in"))
      (node (ref "Y4") (pin "4") (pinfunction "GND_4") (pintype "power_in"))
    )
    (net (code "72") (name "Net-(D43-K-Pad1)") (class "Default")
      (node (ref "D43") (pin "1") (pinfunction "K_1") (pintype "passive"))
      (node (ref "R222") (pin "2") (pinfunction "2_2") (pintype "passive"))
    )
    (net (code "73") (name "Net-(D43-K-Pad4)") (class "Default")
      (node (ref "D43") (pin "4") (pinfunction "K_4") (pintype "passive"))
      (node (ref "R223") (pin "2") (pinfunction "2_2") (pintype "passive"))
    )
    (net (code "74") (name "Net-(D44-K-Pad1)") (class "Default")
      (node (ref "D44") (pin "1") (pinfunction "K_1") (pintype "passive"))
      (node (ref "R224") (pin "1") (pinfunction "1_1") (pintype "passive"))
    )
    (net (code "75") (name "Net-(D44-K-Pad4)") (class "Default")
      (node (ref "D44") (pin "4") (pinfunction "K_4") (pintype "passive"))
      (node (ref "R225") (pin "2") (pinfunction "2_2") (pintype "passive"))
    )
    (net (code "76") (name "Net-(R216-Pad2)") (class "Default")
      (node (ref "R216") (pin "2") (pinfunction "2_2") (pintype "passive"))
      (node (ref "SW2") (pin "1") (pinfunction "1_1") (pintype "passive"))
    )
    (net (code "77") (name "Net-(R217-Pad2)") (class "Default")
      (node (ref "R217") (pin "2") (pinfunction "2_2") (pintype "passive"))
      (node (ref "SW3") (pin "1") (pinfunction "1_1") (pintype "passive"))
    )
    (net (code "78") (name "Net-(TP63-TP)") (class "Default")
      (node (ref "C203") (pin "2") (pinfunction "2_2") (pintype "passive"))
      (node (ref "C204") (pin "2") (pinfunction "2_2") (pintype "passive"))
      (node (ref "TP63") (pin "1") (pinfunction "TP_1") (pintype "passive"))
      (node (ref "U22") (pin "48") (pinfunction "VCAP_48") (pintype "power_in"))
    )
    (net (code "79") (name "Net-(TP64-TP)") (class "Default")
      (node (ref "C205") (pin "2") (pinfunction "2_2") (pintype "passive"))
      (node (ref "C206") (pin "2") (pinfunction "2_2") (pintype "passive"))
      (node (ref "TP64") (pin "1") (pinfunction "TP_1") (pintype "passive"))
      (node (ref "U22") (pin "73") (pinfunction "VCAP_73") (pintype "power_in"))
    )
    (net (code "80") (name "unconnected-(J13-Pad7)") (class "Default")
      (node (ref "J13") (pin "7") (pinfunction "7_7") (pintype "input+no_connect"))
    )
    (net (code "81") (name "unconnected-(J13-Pad8)") (class "Default")
      (node (ref "J13") (pin "8") (pinfunction "8_8") (pintype "input+no_connect"))
    )
    (net (code "82") (name "unconnected-(J13-Pad9)") (class "Default")
      (node (ref "J13") (pin "9") (pinfunction "9_9") (pintype "input+no_connect"))
    )
    (net (code "83") (name "unconnected-(U22B-PA0-Pad22)") (class "Default")
      (node (ref "U22") (pin "22") (pinfunction "PA0_22") (pintype "bidirectional"))
    )
    (net (code "84") (name "unconnected-(U22B-PA1-Pad23)") (class "Default")
      (node (ref "U22") (pin "23") (pinfunction "PA1_23") (pintype "bidirectional"))
    )
    (net (code "85") (name "unconnected-(U22B-PA2-Pad24)") (class "Default")
      (node (ref "U22") (pin "24") (pinfunction "PA2_24") (pintype "bidirectional"))
    )
    (net (code "86") (name "unconnected-(U22B-PA3-Pad25)") (class "Default")
      (node (ref "U22") (pin "25") (pinfunction "PA3_25") (pintype "bidirectional"))
    )
    (net (code "87") (name "unconnected-(U22B-PA15-Pad77)") (class "Default")
      (node (ref "U22") (pin "77") (pinfunction "PA15_77") (pintype "bidirectional"))
    )
    (net (code "88") (name "unconnected-(U22B-PB2-Pad36)") (class "Default")
      (node (ref "U22") (pin "36") (pinfunction "PB2_36") (pintype "bidirectional"))
    )
    (net (code "89") (name "unconnected-(U22B-PB4-Pad90)") (class "Default")
      (node (ref "U22") (pin "90") (pinfunction "PB4_90") (pintype "bidirectional"))
    )
    (net (code "90") (name "unconnected-(U22B-PB5-Pad91)") (class "Default")
      (node (ref "U22") (pin "91") (pinfunction "PB5_91") (pintype "bidirectional"))
    )
    (net (code "91") (name "unconnected-(U22B-PB15-Pad54)") (class "Default")
      (node (ref "U22") (pin "54") (pinfunction "PB15_54") (pintype "bidirectional"))
    )
    (net (code "92") (name "unconnected-(U22B-PC0-Pad15)") (class "Default")
      (node (ref "U22") (pin "15") (pinfunction "PC0_15") (pintype "bidirectional"))
    )
    (net (code "93") (name "unconnected-(U22B-PC1-Pad16)") (class "Default")
      (node (ref "U22") (pin "16") (pinfunction "PC1_16") (pintype "bidirectional"))
    )
    (net (code "94") (name "unconnected-(U22B-PC2_C-Pad17)") (class "Default")
      (node (ref "U22") (pin "17") (pinfunction "PC2_C_17") (pintype "bidirectional"))
    )
    (net (code "95") (name "unconnected-(U22B-PC3_C-Pad18)") (class "Default")
      (node (ref "U22") (pin "18") (pinfunction "PC3_C_18") (pintype "bidirectional"))
    )
    (net (code "96") (name "unconnected-(U22B-PC5-Pad33)") (class "Default")
      (node (ref "U22") (pin "33") (pinfunction "PC5_33") (pintype "bidirectional"))
    )
    (net (code "97") (name "unconnected-(U22B-PC6-Pad63)") (class "Default")
      (node (ref "U22") (pin "63") (pinfunction "PC6_63") (pintype "bidirectional"))
    )
    (net (code "98") (name "unconnected-(U22B-PC7-Pad64)") (class "Default")
      (node (ref "U22") (pin "64") (pinfunction "PC7_64") (pintype "bidirectional"))
    )
    (net (code "99") (name "unconnected-(U22B-PC8-Pad65)") (class "Default")
      (node (ref "U22") (pin "65") (pinfunction "PC8_65") (pintype "bidirectional"))
    )
    (net (code "100") (name "unconnected-(U22B-PC10-Pad78)") (class "Default")
      (node (ref "U22") (pin "78") (pinfunction "PC10_78") (pintype "bidirectional"))
    )
    (net (code "101") (name "unconnected-(U22B-PC11-Pad79)") (class "Default")
      (node (ref "U22") (pin "79") (pinfunction "PC11_79") (pintype "bidirectional"))
    )
    (net (code "102") (name "unconnected-(U22B-PC12-Pad80)") (class "Default")
      (node (ref "U22") (pin "80") (pinfunction "PC12_80") (pintype "bidirectional"))
    )
    (net (code "103") (name "unconnected-(U22B-PC13-Pad7)") (class "Default")
      (node (ref "U22") (pin "7") (pinfunction "PC13_7") (pintype "bidirectional"))
    )
    (net (code "104") (name "unconnected-(U22B-PD0-Pad81)") (class "Default")
      (node (ref "U22") (pin "81") (pinfunction "PD0_81") (pintype "bidirectional"))
    )
    (net (code "105") (name "unconnected-(U22B-PD1-Pad82)") (class "Default")
      (node (ref "U22") (pin "82") (pinfunction "PD1_82") (pintype "bidirectional"))
    )
    (net (code "106") (name "unconnected-(U22B-PD2-Pad83)") (class "Default")
      (node (ref "U22") (pin "83") (pinfunction "PD2_83") (pintype "bidirectional"))
    )
    (net (code "107") (name "unconnected-(U22B-PD3-Pad84)") (class "Default")
      (node (ref "U22") (pin "84") (pinfunction "PD3_84") (pintype "bidirectional"))
    )
    (net (code "108") (name "unconnected-(U22B-PD4-Pad85)") (class "Default")
      (node (ref "U22") (pin "85") (pinfunction "PD4_85") (pintype "bidirectional"))
    )
    (net (code "109") (name "unconnected-(U22B-PD5-Pad86)") (class "Default")
      (node (ref "U22") (pin "86") (pinfunction "PD5_86") (pintype "bidirectional"))
    )
    (net (code "110") (name "unconnected-(U22B-PD6-Pad87)") (class "Default")
      (node (ref "U22") (pin "87") (pinfunction "PD6_87") (pintype "bidirectional"))
    )
    (net (code "111") (name "unconnected-(U22B-PD7-Pad88)") (class "Default")
      (node (ref "U22") (pin "88") (pinfunction "PD7_88") (pintype "bidirectional"))
    )
    (net (code "112") (name "unconnected-(U22B-PD8-Pad55)") (class "Default")
      (node (ref "U22") (pin "55") (pinfunction "PD8_55") (pintype "bidirectional"))
    )
    (net (code "113") (name "unconnected-(U22B-PD9-Pad56)") (class "Default")
      (node (ref "U22") (pin "56") (pinfunction "PD9_56") (pintype "bidirectional"))
    )
    (net (code "114") (name "unconnected-(U22B-PD10-Pad57)") (class "Default")
      (node (ref "U22") (pin "57") (pinfunction "PD10_57") (pintype "bidirectional"))
    )
    (net (code "115") (name "unconnected-(U22B-PD11-Pad58)") (class "Default")
      (node (ref "U22") (pin "58") (pinfunction "PD11_58") (pintype "bidirectional"))
    )
    (net (code "116") (name "unconnected-(U22B-PD12-Pad59)") (class "Default")
      (node (ref "U22") (pin "59") (pinfunction "PD12_59") (pintype "bidirectional"))
    )
    (net (code "117") (name "unconnected-(U22B-PD13-Pad60)") (class "Default")
      (node (ref "U22") (pin "60") (pinfunction "PD13_60") (pintype "bidirectional"))
    )
    (net (code "118") (name "unconnected-(U22B-PD14-Pad61)") (class "Default")
      (node (ref "U22") (pin "61") (pinfunction "PD14_61") (pintype "bidirectional"))
    )
    (net (code "119") (name "unconnected-(U22B-PD15-Pad62)") (class "Default")
      (node (ref "U22") (pin "62") (pinfunction "PD15_62") (pintype "bidirectional"))
    )
    (net (code "120") (name "unconnected-(U22B-PE2-Pad1)") (class "Default")
      (node (ref "U22") (pin "1") (pinfunction "PE2_1") (pintype "bidirectional"))
    )
    (net (code "121") (name "unconnected-(U22B-PE4-Pad3)") (class "Default")
      (node (ref "U22") (pin "3") (pinfunction "PE4_3") (pintype "bidirectional"))
    )
    (net (code "122") (name "unconnected-(U22B-PE5-Pad4)") (class "Default")
      (node (ref "U22") (pin "4") (pinfunction "PE5_4") (pintype "bidirectional"))
    )
    (net (code "123") (name "unconnected-(U22B-PE6-Pad5)") (class "Default")
      (node (ref "U22") (pin "5") (pinfunction "PE6_5") (pintype "bidirectional"))
    )
    (net (code "124") (name "unconnected-(U22B-PE7-Pad37)") (class "Default")
      (node (ref "U22") (pin "37") (pinfunction "PE7_37") (pintype "bidirectional"))
    )
    (net (code "125") (name "unconnected-(U22B-PE8-Pad38)") (class "Default")
      (node (ref "U22") (pin "38") (pinfunction "PE8_38") (pintype "bidirectional"))
    )
    (net (code "126") (name "unconnected-(U22B-PE9-Pad39)") (class "Default")
      (node (ref "U22") (pin "39") (pinfunction "PE9_39") (pintype "bidirectional"))
    )
    (net (code "127") (name "unconnected-(U22B-PE10-Pad40)") (class "Default")
      (node (ref "U22") (pin "40") (pinfunction "PE10_40") (pintype "bidirectional"))
    )
  )
)
